# Diode_Controllers.net
KiCad netlist of a schematic drawn in Altium Designer
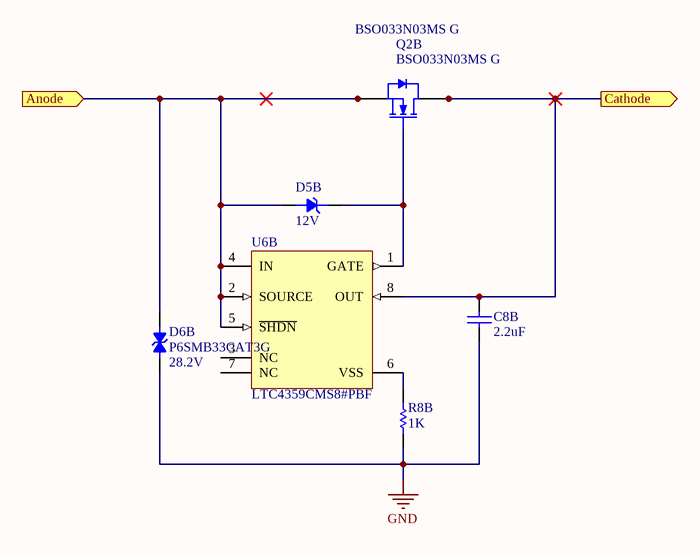
[diagram p0: Diode Controllers.SchDoc]

(export (version "E")
  (design (tool "Eeschema 10.0.6"))
  (components
    (comp (ref "C8B")
      (value "2.2uF")
      (footprint "C1206")
      (description "Ceramic MLCC, Taiyo Yuden, X7R Dielectric")
      (fields
        (field (name "MANUFACTURER PART NUMBER") "UMK316F225ZG-T")
        (field (name "Comment") "2.2uF, C1206 TY , Ceramic MLCC")
      )
      (libsource (lib "Capacitors SchLib") (part "2.2uF, C1206 TY , Ceramic MLCC"))
    )
    (comp (ref "D5B")
      (value "MM5Z12VT1G, 12V Zener")
      (footprint "ONSC-SOD-523-2-502-01_C_V")
      (description "Zener diode")
      (fields
        (field (name "MANUFACTURER PART NUMBER") "MM5Z12VT1G")
        (field (name "ZENER VOLTAGE VZ TYP") "12V")
      )
      (libsource (lib "URC") (part "MM5Z12VT1G, 12V Zener"))
    )
    (comp (ref "D6B")
      (value "28.2V")
      (footprint "ONSC-SMB-2-403A-03_H_V")
      (description "Bidirectional Zener diode")
      (fields
        (field (name "MANUFACTURER PART NUMBER") "P6SMB33CAT3G")
        (field (name "Comment") "Bidirectional Zener")
      )
      (libsource (lib "URC") (part "P6SMB33CAT3G 28.2V Bidirectional Zener"))
    )
    (comp (ref "Q2B")
      (value "BSO033N03MS G")
      (footprint "INF-PG-DSO-8-3_N")
      (fields (field (name "MANUFACTURER PART NUMBER") "BSO033N03MS G"))
      (libsource (lib "Infineon Power MOSFET") (part "BSO033N03MS G"))
    )
    (comp (ref "R8B")
      (value "1K")
      (footprint "R0603")
      (description "Resistor")
      (fields (field (name "TOLERANCE") "5%") (field (name "MANUFACTURER PART NUMBER") "RC0603JR-131KL"))
      (libsource (lib "Resistors SchLib") (part "1k, 5%, 100mW, Yageo, R0603"))
    )
    (comp (ref "U6B")
      (value "LTC4359CMS8#PBF")
      (footprint "LT-MS8-8_N")
      (fields (field (name "MANUFACTURER PART NUMBER") "LTC4359CMS8#PBF"))
      (libsource (lib "Linear Technology Power Management Power Control") (part "LTC4359CMS8#PBF"))
    )
  )
  (nets
    (net (code "1") (name "/Anode") (class "Default")
      (node (ref "D5B") (pin "1") (pinfunction "1_1") (pintype "passive"))
      (node (ref "D6B") (pin "1") (pinfunction "1_1") (pintype "passive"))
      (node (ref "Q2B") (pin "1") (pinfunction "SOURCE_1") (pintype "passive"))
      (node (ref "Q2B") (pin "2") (pinfunction "SOURCE_2") (pintype "passive"))
      (node (ref "Q2B") (pin "3") (pinfunction "SOURCE_3") (pintype "passive"))
      (node (ref "U6B") (pin "2") (pinfunction "SOURCE_2") (pintype "input"))
      (node (ref "U6B") (pin "4") (pinfunction "IN_4") (pintype "power_in"))
      (node (ref "U6B") (pin "5") (pinfunction "~{SHDN}_5") (pintype "input"))
    )
    (net (code "2") (name "/Cathode") (class "Default")
      (node (ref "C8B") (pin "2") (pinfunction "2_2") (pintype "passive"))
      (node (ref "Q2B") (pin "5") (pinfunction "DRAIN_5") (pintype "passive"))
      (node (ref "Q2B") (pin "6") (pinfunction "DRAIN_6") (pintype "passive"))
      (node (ref "Q2B") (pin "7") (pinfunction "DRAIN_7") (pintype "passive"))
      (node (ref "Q2B") (pin "8") (pinfunction "DRAIN_8") (pintype "passive"))
      (node (ref "U6B") (pin "8") (pinfunction "OUT_8") (pintype "input"))
    )
    (net (code "3") (name "GND") (class "Default")
      (node (ref "C8B") (pin "1") (pinfunction "+_1") (pintype "passive"))
      (node (ref "D6B") (pin "2") (pinfunction "2_2") (pintype "passive"))
      (node (ref "R8B") (pin "1") (pinfunction "1_1") (pintype "passive"))
    )
    (net (code "4") (name "Net-(Q2B-GATE)") (class "Default")
      (node (ref "D5B") (pin "2") (pinfunction "2_2") (pintype "passive"))
      (node (ref "Q2B") (pin "4") (pinfunction "GATE_4") (pintype "passive"))
      (node (ref "U6B") (pin "1") (pinfunction "GATE_1") (pintype "output"))
    )
    (net (code "5") (name "Net-(U6B-VSS)") (class "Default")
      (node (ref "R8B") (pin "2") (pinfunction "2_2") (pintype "passive"))
      (node (ref "U6B") (pin "6") (pinfunction "VSS_6") (pintype "power_in"))
    )
    (net (code "6") (name "unconnected-(U6B-NC-Pad3)") (class "Default")
      (node (ref "U6B") (pin "3") (pinfunction "NC_3") (pintype "passive"))
    )
    (net (code "7") (name "unconnected-(U6B-NC-Pad7)") (class "Default")
      (node (ref "U6B") (pin "7") (pinfunction "NC_7") (pintype "passive"))
    )
  )
)
